# BV100011_ControlDI.net
KiCad netlist of a schematic drawn in Altium Designer
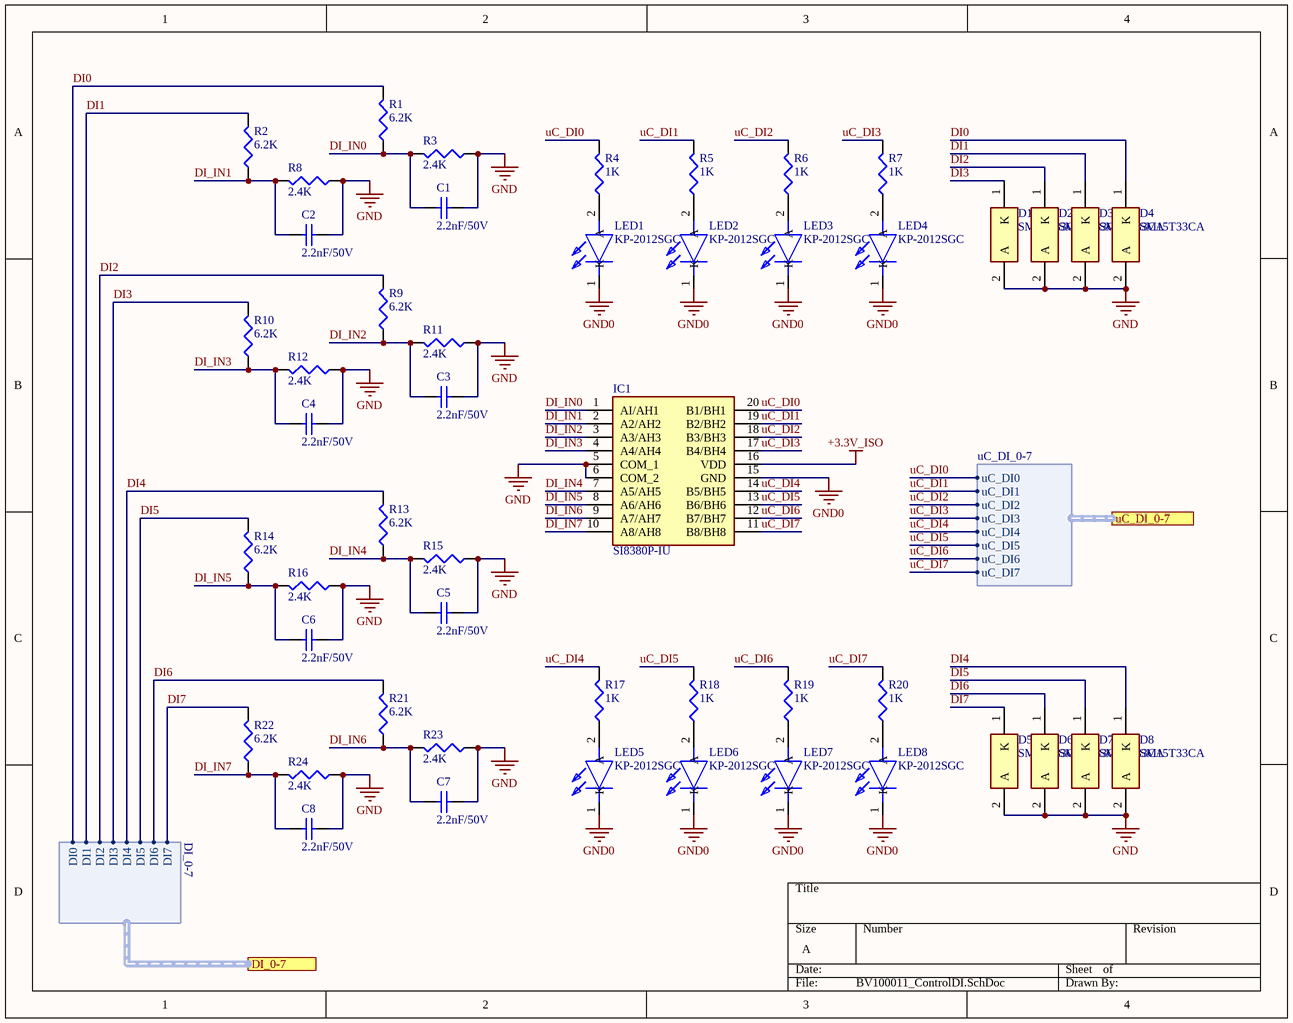
[diagram p0: BV100011_ControlDI.SchDoc]

(export (version "E")
  (design (tool "Eeschema 10.0.6"))
  (components
    (comp (ref "C1")
      (value "2.2nF/50V")
      (footprint "C1210")
      (description "Capacitor (Semiconductor SIM Model)")
      (fields (field (name "PUBLISHER") "Altium Limited"))
      (libsource (lib "Miscellaneous Devices") (part "Cap Semi"))
    )
    (comp (ref "C2")
      (value "2.2nF/50V")
      (footprint "C1210")
      (description "Capacitor (Semiconductor SIM Model)")
      (fields (field (name "PUBLISHER") "Altium Limited"))
      (libsource (lib "Miscellaneous Devices") (part "Cap Semi"))
    )
    (comp (ref "C3")
      (value "2.2nF/50V")
      (footprint "C1210")
      (description "Capacitor (Semiconductor SIM Model)")
      (fields (field (name "PUBLISHER") "Altium Limited"))
      (libsource (lib "Miscellaneous Devices") (part "Cap Semi"))
    )
    (comp (ref "C4")
      (value "2.2nF/50V")
      (footprint "C1210")
      (description "Capacitor (Semiconductor SIM Model)")
      (fields (field (name "PUBLISHER") "Altium Limited"))
      (libsource (lib "Miscellaneous Devices") (part "Cap Semi"))
    )
    (comp (ref "C5")
      (value "2.2nF/50V")
      (footprint "C1210")
      (description "Capacitor (Semiconductor SIM Model)")
      (fields (field (name "PUBLISHER") "Altium Limited"))
      (libsource (lib "Miscellaneous Devices") (part "Cap Semi"))
    )
    (comp (ref "C6")
      (value "2.2nF/50V")
      (footprint "C1210")
      (description "Capacitor (Semiconductor SIM Model)")
      (fields (field (name "PUBLISHER") "Altium Limited"))
      (libsource (lib "Miscellaneous Devices") (part "Cap Semi"))
    )
    (comp (ref "C7")
      (value "2.2nF/50V")
      (footprint "C1210")
      (description "Capacitor (Semiconductor SIM Model)")
      (fields (field (name "PUBLISHER") "Altium Limited"))
      (libsource (lib "Miscellaneous Devices") (part "Cap Semi"))
    )
    (comp (ref "C8")
      (value "2.2nF/50V")
      (footprint "C1210")
      (description "Capacitor (Semiconductor SIM Model)")
      (fields (field (name "PUBLISHER") "Altium Limited"))
      (libsource (lib "Miscellaneous Devices") (part "Cap Semi"))
    )
    (comp (ref "D1")
      (value "SM15T33CA")
      (footprint "DIONM8059X265N")
      (description "Diode")
      (fields (field (name "MOUSER PART NUMBER") "511-SM15T33CA") (field (name "RS PART NUMBER") "9196428"))
      (libsource (lib "SM15T33CA") (part "SM15T33CA"))
    )
    (comp (ref "D2")
      (value "SM15T33CA")
      (footprint "DIONM8059X265N")
      (description "Diode")
      (fields (field (name "MOUSER PART NUMBER") "511-SM15T33CA") (field (name "RS PART NUMBER") "9196428"))
      (libsource (lib "SM15T33CA") (part "SM15T33CA"))
    )
    (comp (ref "D3")
      (value "SM15T33CA")
      (footprint "DIONM8059X265N")
      (description "Diode")
      (fields (field (name "MOUSER PART NUMBER") "511-SM15T33CA") (field (name "RS PART NUMBER") "9196428"))
      (libsource (lib "SM15T33CA") (part "SM15T33CA"))
    )
    (comp (ref "D4")
      (value "SM15T33CA")
      (footprint "DIONM8059X265N")
      (description "Diode")
      (fields (field (name "MOUSER PART NUMBER") "511-SM15T33CA") (field (name "RS PART NUMBER") "9196428"))
      (libsource (lib "SM15T33CA") (part "SM15T33CA"))
    )
    (comp (ref "D5")
      (value "SM15T33CA")
      (footprint "DIONM8059X265N")
      (description "Diode")
      (fields (field (name "MOUSER PART NUMBER") "511-SM15T33CA") (field (name "RS PART NUMBER") "9196428"))
      (libsource (lib "SM15T33CA") (part "SM15T33CA"))
    )
    (comp (ref "D6")
      (value "SM15T33CA")
      (footprint "DIONM8059X265N")
      (description "Diode")
      (fields (field (name "MOUSER PART NUMBER") "511-SM15T33CA") (field (name "RS PART NUMBER") "9196428"))
      (libsource (lib "SM15T33CA") (part "SM15T33CA"))
    )
    (comp (ref "D7")
      (value "SM15T33CA")
      (footprint "DIONM8059X265N")
      (description "Diode")
      (fields (field (name "MOUSER PART NUMBER") "511-SM15T33CA") (field (name "RS PART NUMBER") "9196428"))
      (libsource (lib "SM15T33CA") (part "SM15T33CA"))
    )
    (comp (ref "D8")
      (value "SM15T33CA")
      (footprint "DIONM8059X265N")
      (description "Diode")
      (fields (field (name "MOUSER PART NUMBER") "511-SM15T33CA") (field (name "RS PART NUMBER") "9196428"))
      (libsource (lib "SM15T33CA") (part "SM15T33CA"))
    )
    (comp (ref "IC1")
      (value "SI8380P-IU")
      (footprint "SOP64P600X175-20N")
      (description "Integrated Circuit")
      (fields (field (name "MOUSER PART NUMBER") "634-SI8380P-IU"))
      (libsource (lib "SI8380P-IU") (part "SI8380P-IU"))
    )
    (comp (ref "LED1")
      (value "KP-2012SGC")
      (footprint "LEDC2012X110N")
      (description "LED")
      (fields (field (name "RS PART NUMBER") "4663807"))
      (libsource (lib "POWER_LED") (part "KP-2012SGC"))
    )
    (comp (ref "LED2")
      (value "KP-2012SGC")
      (footprint "LEDC2012X110N")
      (description "LED")
      (fields (field (name "RS PART NUMBER") "4663807"))
      (libsource (lib "POWER_LED") (part "KP-2012SGC"))
    )
    (comp (ref "LED3")
      (value "KP-2012SGC")
      (footprint "LEDC2012X110N")
      (description "LED")
      (fields (field (name "RS PART NUMBER") "4663807"))
      (libsource (lib "POWER_LED") (part "KP-2012SGC"))
    )
    (comp (ref "LED4")
      (value "KP-2012SGC")
      (footprint "LEDC2012X110N")
      (description "LED")
      (fields (field (name "RS PART NUMBER") "4663807"))
      (libsource (lib "POWER_LED") (part "KP-2012SGC"))
    )
    (comp (ref "LED5")
      (value "KP-2012SGC")
      (footprint "LEDC2012X110N")
      (description "LED")
      (fields (field (name "RS PART NUMBER") "4663807"))
      (libsource (lib "POWER_LED") (part "KP-2012SGC"))
    )
    (comp (ref "LED6")
      (value "KP-2012SGC")
      (footprint "LEDC2012X110N")
      (description "LED")
      (fields (field (name "RS PART NUMBER") "4663807"))
      (libsource (lib "POWER_LED") (part "KP-2012SGC"))
    )
    (comp (ref "LED7")
      (value "KP-2012SGC")
      (footprint "LEDC2012X110N")
      (description "LED")
      (fields (field (name "RS PART NUMBER") "4663807"))
      (libsource (lib "POWER_LED") (part "KP-2012SGC"))
    )
    (comp (ref "LED8")
      (value "KP-2012SGC")
      (footprint "LEDC2012X110N")
      (description "LED")
      (fields (field (name "RS PART NUMBER") "4663807"))
      (libsource (lib "POWER_LED") (part "KP-2012SGC"))
    )
    (comp (ref "R1")
      (value "6.2K")
      (footprint "12Z-2010")
      (description "Resistor")
      (fields (field (name "PUBLISHER") "Altium Limited"))
      (libsource (lib "Miscellaneous Devices") (part "Res3"))
    )
    (comp (ref "R2")
      (value "6.2K")
      (footprint "12Z-2010")
      (description "Resistor")
      (fields (field (name "PUBLISHER") "Altium Limited"))
      (libsource (lib "Miscellaneous Devices") (part "Res3"))
    )
    (comp (ref "R3")
      (value "2.4K")
      (footprint "12Z-2010")
      (description "Resistor")
      (fields (field (name "PUBLISHER") "Altium Limited"))
      (libsource (lib "Miscellaneous Devices") (part "Res3"))
    )
    (comp (ref "R4")
      (value "1K")
      (footprint "0402")
      (description "Resistor")
      (fields (field (name "PUBLISHER") "Altium Limited"))
      (libsource (lib "Miscellaneous Devices") (part "Res3"))
    )
    (comp (ref "R5")
      (value "1K")
      (footprint "0402")
      (description "Resistor")
      (fields (field (name "PUBLISHER") "Altium Limited"))
      (libsource (lib "Miscellaneous Devices") (part "Res3"))
    )
    (comp (ref "R6")
      (value "1K")
      (footprint "0402")
      (description "Resistor")
      (fields (field (name "PUBLISHER") "Altium Limited"))
      (libsource (lib "Miscellaneous Devices") (part "Res3"))
    )
    (comp (ref "R7")
      (value "1K")
      (footprint "0402")
      (description "Resistor")
      (fields (field (name "PUBLISHER") "Altium Limited"))
      (libsource (lib "Miscellaneous Devices") (part "Res3"))
    )
    (comp (ref "R8")
      (value "2.4K")
      (footprint "12Z-2010")
      (description "Resistor")
      (fields (field (name "PUBLISHER") "Altium Limited"))
      (libsource (lib "Miscellaneous Devices") (part "Res3"))
    )
    (comp (ref "R9")
      (value "6.2K")
      (footprint "12Z-2010")
      (description "Resistor")
      (fields (field (name "PUBLISHER") "Altium Limited"))
      (libsource (lib "Miscellaneous Devices") (part "Res3"))
    )
    (comp (ref "R10")
      (value "6.2K")
      (footprint "12Z-2010")
      (description "Resistor")
      (fields (field (name "PUBLISHER") "Altium Limited"))
      (libsource (lib "Miscellaneous Devices") (part "Res3"))
    )
    (comp (ref "R11")
      (value "2.4K")
      (footprint "12Z-2010")
      (description "Resistor")
      (fields (field (name "PUBLISHER") "Altium Limited"))
      (libsource (lib "Miscellaneous Devices") (part "Res3"))
    )
    (comp (ref "R12")
      (value "2.4K")
      (footprint "12Z-2010")
      (description "Resistor")
      (fields (field (name "PUBLISHER") "Altium Limited"))
      (libsource (lib "Miscellaneous Devices") (part "Res3"))
    )
    (comp (ref "R13")
      (value "6.2K")
      (footprint "12Z-2010")
      (description "Resistor")
      (fields (field (name "PUBLISHER") "Altium Limited"))
      (libsource (lib "Miscellaneous Devices") (part "Res3"))
    )
    (comp (ref "R14")
      (value "6.2K")
      (footprint "12Z-2010")
      (description "Resistor")
      (fields (field (name "PUBLISHER") "Altium Limited"))
      (libsource (lib "Miscellaneous Devices") (part "Res3"))
    )
    (comp (ref "R15")
      (value "2.4K")
      (footprint "12Z-2010")
      (description "Resistor")
      (fields (field (name "PUBLISHER") "Altium Limited"))
      (libsource (lib "Miscellaneous Devices") (part "Res3"))
    )
    (comp (ref "R16")
      (value "2.4K")
      (footprint "12Z-2010")
      (description "Resistor")
      (fields (field (name "PUBLISHER") "Altium Limited"))
      (libsource (lib "Miscellaneous Devices") (part "Res3"))
    )
    (comp (ref "R17")
      (value "1K")
      (footprint "0402")
      (description "Resistor")
      (fields (field (name "PUBLISHER") "Altium Limited"))
      (libsource (lib "Miscellaneous Devices") (part "Res3"))
    )
    (comp (ref "R18")
      (value "1K")
      (footprint "0402")
      (description "Resistor")
      (fields (field (name "PUBLISHER") "Altium Limited"))
      (libsource (lib "Miscellaneous Devices") (part "Res3"))
    )
    (comp (ref "R19")
      (value "1K")
      (footprint "0402")
      (description "Resistor")
      (fields (field (name "PUBLISHER") "Altium Limited"))
      (libsource (lib "Miscellaneous Devices") (part "Res3"))
    )
    (comp (ref "R20")
      (value "1K")
      (footprint "0402")
      (description "Resistor")
      (fields (field (name "PUBLISHER") "Altium Limited"))
      (libsource (lib "Miscellaneous Devices") (part "Res3"))
    )
    (comp (ref "R21")
      (value "6.2K")
      (footprint "12Z-2010")
      (description "Resistor")
      (fields (field (name "PUBLISHER") "Altium Limited"))
      (libsource (lib "Miscellaneous Devices") (part "Res3"))
    )
    (comp (ref "R22")
      (value "6.2K")
      (footprint "12Z-2010")
      (description "Resistor")
      (fields (field (name "PUBLISHER") "Altium Limited"))
      (libsource (lib "Miscellaneous Devices") (part "Res3"))
    )
    (comp (ref "R23")
      (value "2.4K")
      (footprint "12Z-2010")
      (description "Resistor")
      (fields (field (name "PUBLISHER") "Altium Limited"))
      (libsource (lib "Miscellaneous Devices") (part "Res3"))
    )
    (comp (ref "R24")
      (value "2.4K")
      (footprint "12Z-2010")
      (description "Resistor")
      (fields (field (name "PUBLISHER") "Altium Limited"))
      (libsource (lib "Miscellaneous Devices") (part "Res3"))
    )
  )
  (nets
    (net (code "3") (name "+3.3V_ISO") (class "Default")
      (node (ref "IC1") (pin "16") (pinfunction "VDD_16") (pintype "passive"))
    )
    (net (code "4") (name "/DI0") (class "Default")
      (node (ref "D4") (pin "1") (pinfunction "K_1") (pintype "passive"))
      (node (ref "R1") (pin "2") (pinfunction "2_2") (pintype "passive"))
    )
    (net (code "5") (name "/DI1") (class "Default")
      (node (ref "D3") (pin "1") (pinfunction "K_1") (pintype "passive"))
      (node (ref "R2") (pin "2") (pinfunction "2_2") (pintype "passive"))
    )
    (net (code "6") (name "/DI2") (class "Default")
      (node (ref "D2") (pin "1") (pinfunction "K_1") (pintype "passive"))
      (node (ref "R9") (pin "2") (pinfunction "2_2") (pintype "passive"))
    )
    (net (code "7") (name "/DI3") (class "Default")
      (node (ref "D1") (pin "1") (pinfunction "K_1") (pintype "passive"))
      (node (ref "R10") (pin "2") (pinfunction "2_2") (pintype "passive"))
    )
    (net (code "8") (name "/DI4") (class "Default")
      (node (ref "D8") (pin "1") (pinfunction "K_1") (pintype "passive"))
      (node (ref "R13") (pin "2") (pinfunction "2_2") (pintype "passive"))
    )
    (net (code "9") (name "/DI5") (class "Default")
      (node (ref "D7") (pin "1") (pinfunction "K_1") (pintype "passive"))
      (node (ref "R14") (pin "2") (pinfunction "2_2") (pintype "passive"))
    )
    (net (code "10") (name "/DI6") (class "Default")
      (node (ref "D6") (pin "1") (pinfunction "K_1") (pintype "passive"))
      (node (ref "R21") (pin "2") (pinfunction "2_2") (pintype "passive"))
    )
    (net (code "11") (name "/DI7") (class "Default")
      (node (ref "D5") (pin "1") (pinfunction "K_1") (pintype "passive"))
      (node (ref "R22") (pin "2") (pinfunction "2_2") (pintype "passive"))
    )
    (net (code "12") (name "/DI_IN0") (class "Default")
      (node (ref "C1") (pin "1") (pinfunction "1_1") (pintype "passive"))
      (node (ref "IC1") (pin "1") (pinfunction "AI/AH1_1") (pintype "passive"))
      (node (ref "R1") (pin "1") (pinfunction "1_1") (pintype "passive"))
      (node (ref "R3") (pin "2") (pinfunction "2_2") (pintype "passive"))
    )
    (net (code "13") (name "/DI_IN1") (class "Default")
      (node (ref "C2") (pin "1") (pinfunction "1_1") (pintype "passive"))
      (node (ref "IC1") (pin "2") (pinfunction "A2/AH2_2") (pintype "passive"))
      (node (ref "R2") (pin "1") (pinfunction "1_1") (pintype "passive"))
      (node (ref "R8") (pin "2") (pinfunction "2_2") (pintype "passive"))
    )
    (net (code "14") (name "/DI_IN2") (class "Default")
      (node (ref "C3") (pin "1") (pinfunction "1_1") (pintype "passive"))
      (node (ref "IC1") (pin "3") (pinfunction "A3/AH3_3") (pintype "passive"))
      (node (ref "R11") (pin "2") (pinfunction "2_2") (pintype "passive"))
      (node (ref "R9") (pin "1") (pinfunction "1_1") (pintype "passive"))
    )
    (net (code "15") (name "/DI_IN3") (class "Default")
      (node (ref "C4") (pin "1") (pinfunction "1_1") (pintype "passive"))
      (node (ref "IC1") (pin "4") (pinfunction "A4/AH4_4") (pintype "passive"))
      (node (ref "R10") (pin "1") (pinfunction "1_1") (pintype "passive"))
      (node (ref "R12") (pin "2") (pinfunction "2_2") (pintype "passive"))
    )
    (net (code "16") (name "/DI_IN4") (class "Default")
      (node (ref "C5") (pin "1") (pinfunction "1_1") (pintype "passive"))
      (node (ref "IC1") (pin "7") (pinfunction "A5/AH5_7") (pintype "passive"))
      (node (ref "R13") (pin "1") (pinfunction "1_1") (pintype "passive"))
      (node (ref "R15") (pin "2") (pinfunction "2_2") (pintype "passive"))
    )
    (net (code "17") (name "/DI_IN5") (class "Default")
      (node (ref "C6") (pin "1") (pinfunction "1_1") (pintype "passive"))
      (node (ref "IC1") (pin "8") (pinfunction "A6/AH6_8") (pintype "passive"))
      (node (ref "R14") (pin "1") (pinfunction "1_1") (pintype "passive"))
      (node (ref "R16") (pin "2") (pinfunction "2_2") (pintype "passive"))
    )
    (net (code "18") (name "/DI_IN6") (class "Default")
      (node (ref "C7") (pin "1") (pinfunction "1_1") (pintype "passive"))
      (node (ref "IC1") (pin "9") (pinfunction "A7/AH7_9") (pintype "passive"))
      (node (ref "R21") (pin "1") (pinfunction "1_1") (pintype "passive"))
      (node (ref "R23") (pin "2") (pinfunction "2_2") (pintype "passive"))
    )
    (net (code "19") (name "/DI_IN7") (class "Default")
      (node (ref "C8") (pin "1") (pinfunction "1_1") (pintype "passive"))
      (node (ref "IC1") (pin "10") (pinfunction "A8/AH8_10") (pintype "passive"))
      (node (ref "R22") (pin "1") (pinfunction "1_1") (pintype "passive"))
      (node (ref "R24") (pin "2") (pinfunction "2_2") (pintype "passive"))
    )
    (net (code "20") (name "/uC_DI0") (class "Default")
      (node (ref "IC1") (pin "20") (pinfunction "B1/BH1_20") (pintype "passive"))
      (node (ref "R4") (pin "2") (pinfunction "2_2") (pintype "passive"))
    )
    (net (code "21") (name "/uC_DI1") (class "Default")
      (node (ref "IC1") (pin "19") (pinfunction "B2/BH2_19") (pintype "passive"))
      (node (ref "R5") (pin "2") (pinfunction "2_2") (pintype "passive"))
    )
    (net (code "22") (name "/uC_DI2") (class "Default")
      (node (ref "IC1") (pin "18") (pinfunction "B3/BH3_18") (pintype "passive"))
      (node (ref "R6") (pin "2") (pinfunction "2_2") (pintype "passive"))
    )
    (net (code "23") (name "/uC_DI3") (class "Default")
      (node (ref "IC1") (pin "17") (pinfunction "B4/BH4_17") (pintype "passive"))
      (node (ref "R7") (pin "2") (pinfunction "2_2") (pintype "passive"))
    )
    (net (code "24") (name "/uC_DI4") (class "Default")
      (node (ref "IC1") (pin "14") (pinfunction "B5/BH5_14") (pintype "passive"))
      (node (ref "R17") (pin "2") (pinfunction "2_2") (pintype "passive"))
    )
    (net (code "25") (name "/uC_DI5") (class "Default")
      (node (ref "IC1") (pin "13") (pinfunction "B6/BH6_13") (pintype "passive"))
      (node (ref "R18") (pin "2") (pinfunction "2_2") (pintype "passive"))
    )
    (net (code "26") (name "/uC_DI6") (class "Default")
      (node (ref "IC1") (pin "12") (pinfunction "B7/BH7_12") (pintype "passive"))
      (node (ref "R19") (pin "2") (pinfunction "2_2") (pintype "passive"))
    )
    (net (code "27") (name "/uC_DI7") (class "Default")
      (node (ref "IC1") (pin "11") (pinfunction "B8/BH8_11") (pintype "passive"))
      (node (ref "R20") (pin "2") (pinfunction "2_2") (pintype "passive"))
    )
    (net (code "30") (name "GND") (class "Default")
      (node (ref "C1") (pin "2") (pinfunction "2_2") (pintype "passive"))
      (node (ref "C2") (pin "2") (pinfunction "2_2") (pintype "passive"))
      (node (ref "C3") (pin "2") (pinfunction "2_2") (pintype "passive"))
      (node (ref "C4") (pin "2") (pinfunction "2_2") (pintype "passive"))
      (node (ref "C5") (pin "2") (pinfunction "2_2") (pintype "passive"))
      (node (ref "C6") (pin "2") (pinfunction "2_2") (pintype "passive"))
      (node (ref "C7") (pin "2") (pinfunction "2_2") (pintype "passive"))
      (node (ref "C8") (pin "2") (pinfunction "2_2") (pintype "passive"))
      (node (ref "D1") (pin "2") (pinfunction "A_2") (pintype "passive"))
      (node (ref "D2") (pin "2") (pinfunction "A_2") (pintype "passive"))
      (node (ref "D3") (pin "2") (pinfunction "A_2") (pintype "passive"))
      (node (ref "D4") (pin "2") (pinfunction "A_2") (pintype "passive"))
      (node (ref "D5") (pin "2") (pinfunction "A_2") (pintype "passive"))
      (node (ref "D6") (pin "2") (pinfunction "A_2") (pintype "passive"))
      (node (ref "D7") (pin "2") (pinfunction "A_2") (pintype "passive"))
      (node (ref "D8") (pin "2") (pinfunction "A_2") (pintype "passive"))
      (node (ref "IC1") (pin "5") (pinfunction "COM_1_5") (pintype "passive"))
      (node (ref "IC1") (pin "6") (pinfunction "COM_2_6") (pintype "passive"))
      (node (ref "R11") (pin "1") (pinfunction "1_1") (pintype "passive"))
      (node (ref "R12") (pin "1") (pinfunction "1_1") (pintype "passive"))
      (node (ref "R15") (pin "1") (pinfunction "1_1") (pintype "passive"))
      (node (ref "R16") (pin "1") (pinfunction "1_1") (pintype "passive"))
      (node (ref "R23") (pin "1") (pinfunction "1_1") (pintype "passive"))
      (node (ref "R24") (pin "1") (pinfunction "1_1") (pintype "passive"))
      (node (ref "R3") (pin "1") (pinfunction "1_1") (pintype "passive"))
      (node (ref "R8") (pin "1") (pinfunction "1_1") (pintype "passive"))
    )
    (net (code "31") (name "GND0") (class "Default")
      (node (ref "IC1") (pin "15") (pinfunction "GND_15") (pintype "passive"))
      (node (ref "LED1") (pin "1") (pinfunction "K_1") (pintype "passive"))
      (node (ref "LED2") (pin "1") (pinfunction "K_1") (pintype "passive"))
      (node (ref "LED3") (pin "1") (pinfunction "K_1") (pintype "passive"))
      (node (ref "LED4") (pin "1") (pinfunction "K_1") (pintype "passive"))
      (node (ref "LED5") (pin "1") (pinfunction "K_1") (pintype "passive"))
      (node (ref "LED6") (pin "1") (pinfunction "K_1") (pintype "passive"))
      (node (ref "LED7") (pin "1") (pinfunction "K_1") (pintype "passive"))
      (node (ref "LED8") (pin "1") (pinfunction "K_1") (pintype "passive"))
    )
    (net (code "32") (name "Net-(LED1-A)") (class "Default")
      (node (ref "LED1") (pin "2") (pinfunction "A_2") (pintype "passive"))
      (node (ref "R4") (pin "1") (pinfunction "1_1") (pintype "passive"))
    )
    (net (code "33") (name "Net-(LED2-A)") (class "Default")
      (node (ref "LED2") (pin "2") (pinfunction "A_2") (pintype "passive"))
      (node (ref "R5") (pin "1") (pinfunction "1_1") (pintype "passive"))
    )
    (net (code "34") (name "Net-(LED3-A)") (class "Default")
      (node (ref "LED3") (pin "2") (pinfunction "A_2") (pintype "passive"))
      (node (ref "R6") (pin "1") (pinfunction "1_1") (pintype "passive"))
    )
    (net (code "35") (name "Net-(LED4-A)") (class "Default")
      (node (ref "LED4") (pin "2") (pinfunction "A_2") (pintype "passive"))
      (node (ref "R7") (pin "1") (pinfunction "1_1") (pintype "passive"))
    )
    (net (code "36") (name "Net-(LED5-A)") (class "Default")
      (node (ref "LED5") (pin "2") (pinfunction "A_2") (pintype "passive"))
      (node (ref "R17") (pin "1") (pinfunction "1_1") (pintype "passive"))
    )
    (net (code "37") (name "Net-(LED6-A)") (class "Default")
      (node (ref "LED6") (pin "2") (pinfunction "A_2") (pintype "passive"))
      (node (ref "R18") (pin "1") (pinfunction "1_1") (pintype "passive"))
    )
    (net (code "38") (name "Net-(LED7-A)") (class "Default")
      (node (ref "LED7") (pin "2") (pinfunction "A_2") (pintype "passive"))
      (node (ref "R19") (pin "1") (pinfunction "1_1") (pintype "passive"))
    )
    (net (code "39") (name "Net-(LED8-A)") (class "Default")
      (node (ref "LED8") (pin "2") (pinfunction "A_2") (pintype "passive"))
      (node (ref "R20") (pin "1") (pinfunction "1_1") (pintype "passive"))
    )
  )
)
